# Solar_Power_Management_ESP32.net
KiCad netlist of a schematic drawn in EAGLE
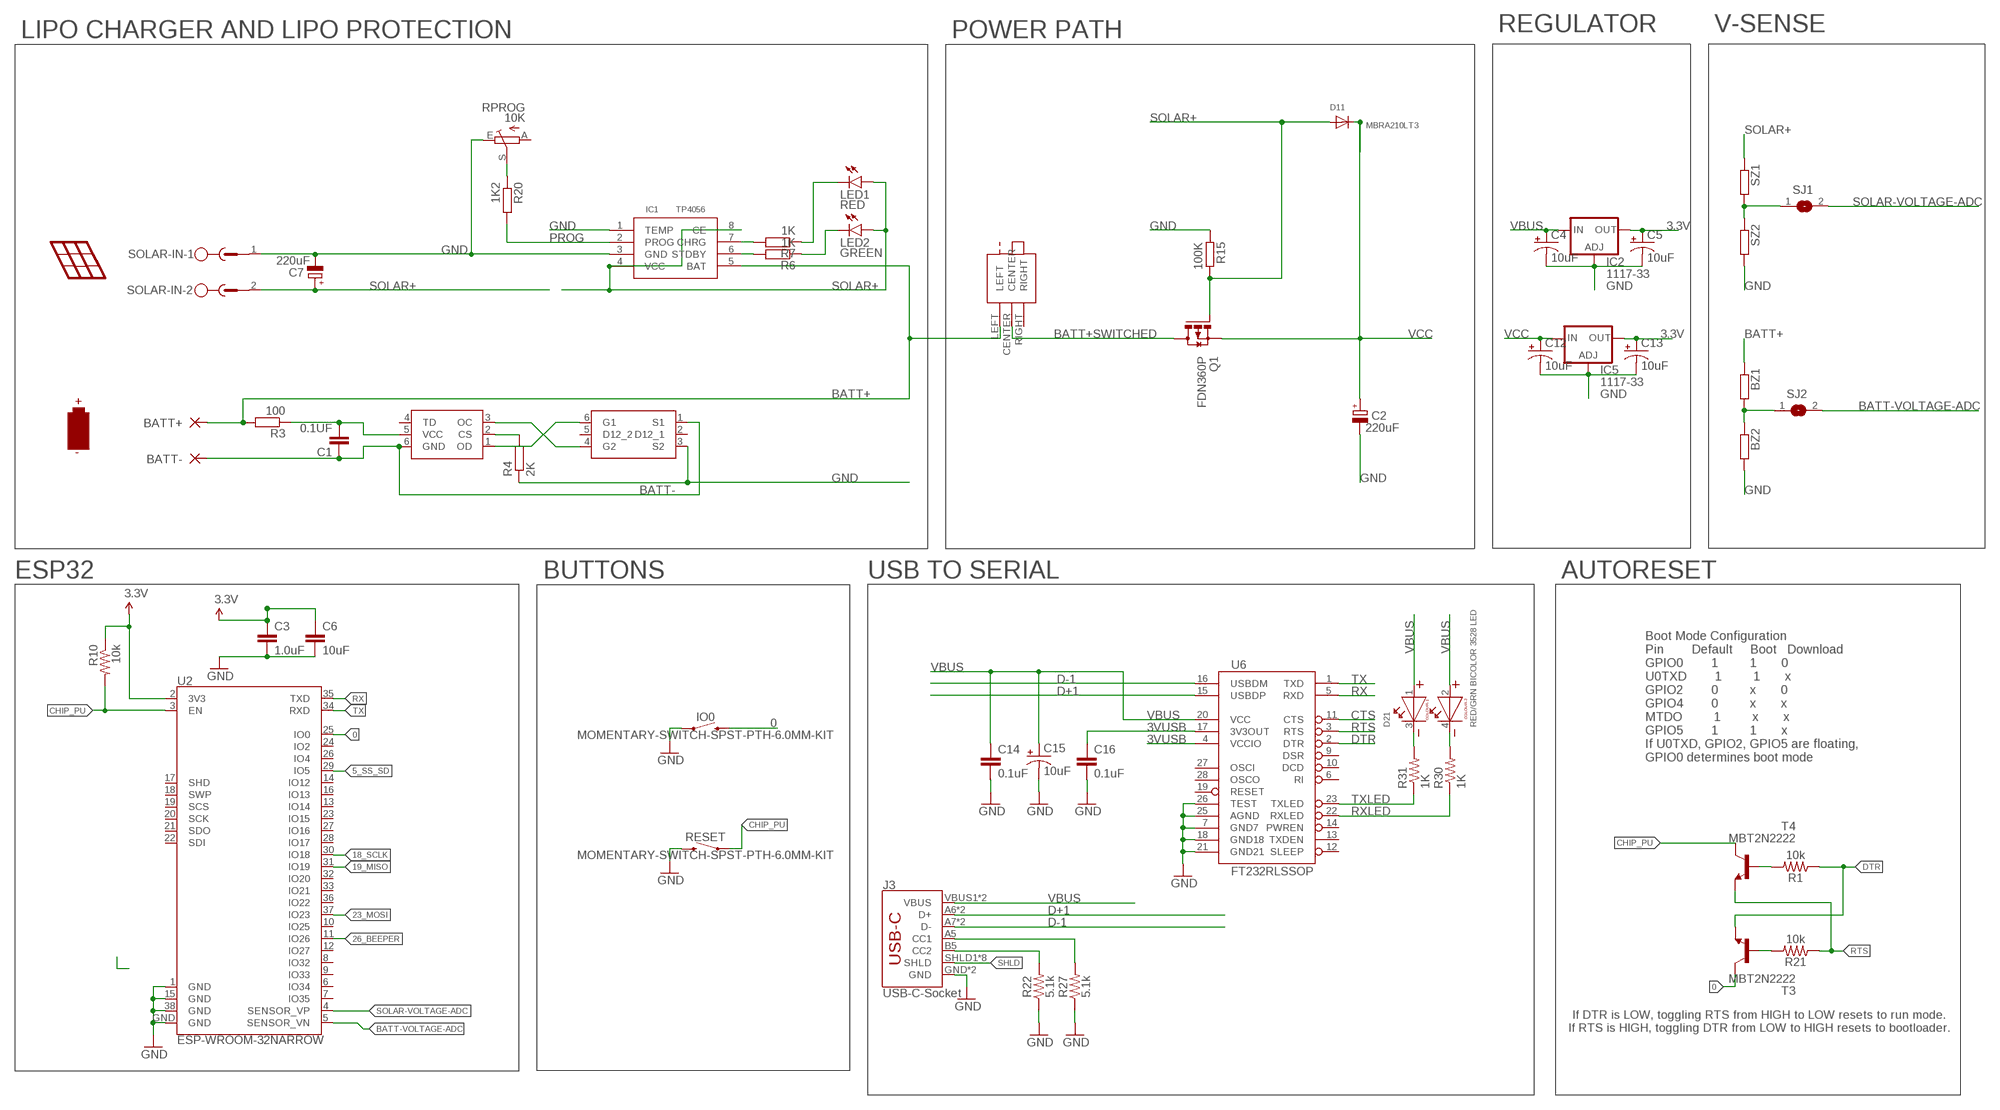
[diagram p0: schematic, sheet 1, part 1 of 2]
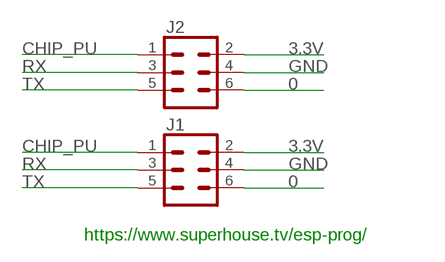
[diagram p1: schematic, sheet 1, part 2 of 2]

(export (version "E")
  (design (tool "Eeschema 10.0.6"))
  (components
    (comp (ref "BATT+")
      (value "3,81/1,4")
      (footprint "eagle-import:3,81_1,4")
      (libsource (lib "eagle-import") (part "3,81/1,4"))
    )
    (comp (ref "BATT-")
      (value "3,81/1,4")
      (footprint "eagle-import:3,81_1,4")
      (libsource (lib "eagle-import") (part "3,81/1,4"))
    )
    (comp (ref "BZ1")
      (value "R-EU_R1206")
      (footprint "eagle-import:R1206")
      (libsource (lib "eagle-import") (part "R-EU_R1206"))
    )
    (comp (ref "BZ2")
      (value "R-EU_R1206")
      (footprint "eagle-import:R1206")
      (libsource (lib "eagle-import") (part "R-EU_R1206"))
    )
    (comp (ref "C1")
      (value "0.1UF")
      (footprint "eagle-import:C1206")
      (libsource (lib "eagle-import") (part "C-EUC1206"))
    )
    (comp (ref "C2")
      (value "220uF")
      (footprint "eagle-import:E3,5-8")
      (libsource (lib "eagle-import") (part "CPOL-EUE3.5-8"))
    )
    (comp (ref "C3")
      (value "1.0uF")
      (footprint "eagle-import:1206")
      (libsource (lib "eagle-import") (part "1.0UF-1206-50V-10%"))
    )
    (comp (ref "C4")
      (value "10uF")
      (footprint "eagle-import:EIA3216")
      (libsource (lib "eagle-import") (part "CAP_POL1206"))
    )
    (comp (ref "C5")
      (value "10uF")
      (footprint "eagle-import:EIA3216")
      (libsource (lib "eagle-import") (part "CAP_POL1206"))
    )
    (comp (ref "C6")
      (value "10uF")
      (footprint "eagle-import:1206")
      (libsource (lib "eagle-import") (part "10UF-1206-6.3V-20%"))
    )
    (comp (ref "C7")
      (value "220uF")
      (footprint "eagle-import:E3,5-8")
      (libsource (lib "eagle-import") (part "CPOL-EUE3.5-8"))
    )
    (comp (ref "C12")
      (value "10uF")
      (footprint "eagle-import:EIA3216")
      (libsource (lib "eagle-import") (part "CAP_POL1206"))
    )
    (comp (ref "C13")
      (value "10uF")
      (footprint "eagle-import:EIA3216")
      (libsource (lib "eagle-import") (part "CAP_POL1206"))
    )
    (comp (ref "C14")
      (value "0.1uF")
      (footprint "eagle-import:0603-CAP")
      (libsource (lib "eagle-import") (part "CAP0603-CAP"))
    )
    (comp (ref "C15")
      (value "10uF")
      (footprint "eagle-import:EIA3216")
      (libsource (lib "eagle-import") (part "CAP_POL1206"))
    )
    (comp (ref "C16")
      (value "0.1uF")
      (footprint "eagle-import:0603-CAP")
      (libsource (lib "eagle-import") (part "CAP0603-CAP"))
    )
    (comp (ref "D11")
      (value "MBRA210LT3")
      (footprint "eagle-import:SMADIODE")
      (libsource (lib "eagle-import") (part "DIODESMA"))
    )
    (comp (ref "D21")
      (value "RED/GRN BICOLOR 3528 LED")
      (footprint "eagle-import:3528")
      (fields
        (field (name "MANUFACTURER") "Würth Elektronik eiSos GmbH")
        (field (name "CREATED-BY") "Christin Otto")
      )
      (libsource (lib "eagle-import") (part "WL-SBTW-150141RB73100-R&B"))
    )
    (comp (ref "IC1")
      (value "TP4056")
      (footprint "eagle-import:SOP-8")
      (libsource (lib "eagle-import") (part "TP4056"))
    )
    (comp (ref "IC2")
      (value "1117-33")
      (footprint "eagle-import:SOT223")
      (libsource (lib "eagle-import") (part "LD117A?S33TR"))
    )
    (comp (ref "IC5")
      (value "1117-33")
      (footprint "eagle-import:SOT223")
      (libsource (lib "eagle-import") (part "LD117A?S33TR"))
    )
    (comp (ref "IO0")
      (value "MOMENTARY-SWITCH-SPST-PTH-6.0MM-KIT")
      (footprint "eagle-import:TACTILE_SWITCH_PTH_6.0MM_KIT")
      (libsource (lib "eagle-import") (part "SparkFun-Switches_535_MOMENTARY-SWITCH-SPST-PTH-6.0MM-KIT"))
    )
    (comp (ref "J1")
      (value "CONN_03X2SHROUD")
      (footprint "eagle-import:2X3-SHROUDED")
      (libsource (lib "eagle-import") (part "CONN_03X2SHROUD"))
    )
    (comp (ref "J2")
      (value "CONN_03X2SHROUD")
      (footprint "eagle-import:2X3-SHROUDED")
      (libsource (lib "eagle-import") (part "CONN_03X2SHROUD"))
    )
    (comp (ref "J3")
      (value "USB-C-Socket")
      (footprint "eagle-import:USB-C-16P")
      (libsource (lib "eagle-import") (part "USB_C16PIN"))
    )
    (comp (ref "LED1")
      (value "RED")
      (footprint "eagle-import:CHIPLED_1206")
      (libsource (lib "eagle-import") (part "LEDCHIPLED_1206"))
    )
    (comp (ref "LED2")
      (value "GREEN")
      (footprint "eagle-import:CHIPLED_1206")
      (libsource (lib "eagle-import") (part "LEDCHIPLED_1206"))
    )
    (comp (ref "Q1")
      (value "FDN360P")
      (footprint "eagle-import:SUPER-SOT3")
      (libsource (lib "eagle-import") (part "FDN360P"))
    )
    (comp (ref "R1")
      (value "10k")
      (footprint "eagle-import:0603")
      (libsource (lib "eagle-import") (part "10KOHM-0603-1/10W-1%"))
    )
    (comp (ref "R3")
      (value "100")
      (footprint "eagle-import:R1206")
      (libsource (lib "eagle-import") (part "R-EU_R1206"))
    )
    (comp (ref "R4")
      (value "2K")
      (footprint "eagle-import:R1206")
      (libsource (lib "eagle-import") (part "R-EU_R1206"))
    )
    (comp (ref "R6")
      (value "1K")
      (footprint "eagle-import:R1206")
      (libsource (lib "eagle-import") (part "R-EU_R1206"))
    )
    (comp (ref "R7")
      (value "1K")
      (footprint "eagle-import:R1206")
      (libsource (lib "eagle-import") (part "R-EU_R1206"))
    )
    (comp (ref "R10")
      (value "10k")
      (footprint "eagle-import:R1206")
      (libsource (lib "eagle-import") (part "R-US_R1206"))
    )
    (comp (ref "R15")
      (value "100K")
      (footprint "eagle-import:R1206")
      (libsource (lib "eagle-import") (part "R-EU_R1206"))
    )
    (comp (ref "R20")
      (value "1K2")
      (footprint "eagle-import:R1206")
      (fields (field (name "SPICEPREFIX") "R"))
      (libsource (lib "eagle-import") (part "R-EU_R1206"))
    )
    (comp (ref "R21")
      (value "10k")
      (footprint "eagle-import:0603")
      (libsource (lib "eagle-import") (part "10KOHM-0603-1/10W-1%"))
    )
    (comp (ref "R22")
      (value "5.1k")
      (footprint "eagle-import:0603@1")
      (libsource (lib "eagle-import") (part "5.1KOHM5.1KOHM-0603-1/10W-1%"))
    )
    (comp (ref "R27")
      (value "5.1k")
      (footprint "eagle-import:0603@1")
      (libsource (lib "eagle-import") (part "5.1KOHM5.1KOHM-0603-1/10W-1%"))
    )
    (comp (ref "R30")
      (value "1K")
      (footprint "eagle-import:0603-RES")
      (libsource (lib "eagle-import") (part "RESISTOR0603-RES"))
    )
    (comp (ref "R31")
      (value "1K")
      (footprint "eagle-import:0603-RES")
      (libsource (lib "eagle-import") (part "RESISTOR0603-RES"))
    )
    (comp (ref "RESET")
      (value "MOMENTARY-SWITCH-SPST-PTH-6.0MM-KIT")
      (footprint "eagle-import:TACTILE_SWITCH_PTH_6.0MM_KIT")
      (libsource (lib "eagle-import") (part "MOMENTARY-SWITCH-SPST-PTH-6.0MM-KIT"))
    )
    (comp (ref "RPROG")
      (value "10K")
      (footprint "eagle-import:B25P")
      (libsource (lib "eagle-import") (part "TRIM_EU-B25P"))
    )
    (comp (ref "SJ1") (value "SJ") (footprint "eagle-import:SJ") (libsource (lib "eagle-import") (part "SJ")))
    (comp (ref "SJ2") (value "SJ") (footprint "eagle-import:SJ") (libsource (lib "eagle-import") (part "SJ")))
    (comp (ref "SOLAR-IN")
      (value "MSTBV2")
      (footprint "eagle-import:MSTBV2")
      (libsource (lib "eagle-import") (part "MSTBV2"))
    )
    (comp (ref "SZ1")
      (value "R-EU_R1206")
      (footprint "eagle-import:R1206")
      (libsource (lib "eagle-import") (part "R-EU_R1206"))
    )
    (comp (ref "SZ2")
      (value "R-EU_R1206")
      (footprint "eagle-import:R1206")
      (libsource (lib "eagle-import") (part "R-EU_R1206"))
    )
    (comp (ref "T3")
      (value "MBT2N2222")
      (footprint "eagle-import:SOT23-BEC")
      (libsource (lib "eagle-import") (part "-NPN-SOT23-BECMMBT2222ALT1"))
    )
    (comp (ref "T4")
      (value "MBT2N2222")
      (footprint "eagle-import:SOT23-BEC")
      (libsource (lib "eagle-import") (part "-NPN-SOT23-BECMMBT2222ALT1"))
    )
    (comp (ref "U$1")
      (value "FS312F-G")
      (footprint "eagle-import:SOT23-6")
      (libsource (lib "eagle-import") (part "FS312F-G"))
    )
    (comp (ref "U$2")
      (value "FS8205")
      (footprint "eagle-import:SOT23-6")
      (libsource (lib "eagle-import") (part "FS8205"))
    )
    (comp (ref "U$3")
      (value "XKBENTERPRISESS-12D11G5R")
      (footprint "eagle-import:XKBENTERPRISESS-12D11G5R")
      (libsource (lib "eagle-import") (part "XKBENTERPRISESS-12D11G5R"))
    )
    (comp (ref "U2")
      (value "ESP-WROOM-32NARROW")
      (footprint "eagle-import:ESP-WROOM-32-NARROW")
      (libsource (lib "eagle-import") (part "ESP-WROOM-32NARROW"))
    )
    (comp (ref "U6")
      (value "FT232RLSSOP")
      (footprint "eagle-import:SSOP28DB")
      (libsource (lib "eagle-import") (part "FT232RLSSOP"))
    )
  )
  (nets
    (net (code "1") (name "/3VUSB") (class "Default")
      (node (ref "C16") (pin "1") (pinfunction "1_1") (pintype "passive"))
      (node (ref "U6") (pin "17") (pinfunction "3V3OUT_17") (pintype "output"))
      (node (ref "U6") (pin "4") (pinfunction "VCCIO_4") (pintype "power_in"))
    )
    (net (code "2") (name "/BATT+") (class "Default")
      (node (ref "BATT+") (pin "1") (pinfunction "P_1") (pintype "passive"))
      (node (ref "BZ1") (pin "1") (pinfunction "1_1") (pintype "passive"))
      (node (ref "IC1") (pin "5") (pinfunction "BAT_5") (pintype "bidirectional"))
      (node (ref "R3") (pin "2") (pinfunction "2_2") (pintype "passive"))
      (node (ref "U$3") (pin "LEFT") (pinfunction "LEFT_LEFT") (pintype "bidirectional"))
    )
    (net (code "3") (name "/BATT+SWITCHED") (class "Default")
      (node (ref "Q1") (pin "3") (pinfunction "D_3") (pintype "passive"))
      (node (ref "U$3") (pin "CENTER") (pinfunction "CENTER_CENTER") (pintype "bidirectional"))
    )
    (net (code "4") (name "/BATT-") (class "Default")
      (node (ref "BATT-") (pin "1") (pinfunction "P_1") (pintype "passive"))
      (node (ref "C1") (pin "1") (pinfunction "1_1") (pintype "passive"))
      (node (ref "U$1") (pin "6") (pinfunction "GND_6") (pintype "bidirectional"))
      (node (ref "U$2") (pin "1") (pinfunction "S1_1") (pintype "bidirectional"))
    )
    (net (code "5") (name "/CTS") (class "Default")
      (node (ref "U6") (pin "11") (pinfunction "CTS_11") (pintype "input"))
    )
    (net (code "6") (name "/D+1") (class "Default")
      (node (ref "J3") (pin "A6") (pinfunction "D+_A6") (pintype "bidirectional"))
      (node (ref "J3") (pin "B6") (pinfunction "D+_B6") (pintype "bidirectional"))
      (node (ref "U6") (pin "15") (pinfunction "USBDP_15") (pintype "bidirectional"))
    )
    (net (code "7") (name "/D-1") (class "Default")
      (node (ref "J3") (pin "A7") (pinfunction "D-_A7") (pintype "bidirectional"))
      (node (ref "J3") (pin "B7") (pinfunction "D-_B7") (pintype "bidirectional"))
      (node (ref "U6") (pin "16") (pinfunction "USBDM_16") (pintype "bidirectional"))
    )
    (net (code "8") (name "/PROG") (class "Default")
      (node (ref "IC1") (pin "2") (pinfunction "PROG_2") (pintype "bidirectional"))
      (node (ref "R20") (pin "2") (pinfunction "2_2") (pintype "passive"))
    )
    (net (code "9") (name "/RXLED") (class "Default")
      (node (ref "R30") (pin "1") (pinfunction "1_1") (pintype "passive"))
      (node (ref "U6") (pin "22") (pinfunction "RXLED_22") (pintype "input"))
    )
    (net (code "10") (name "/SOLAR+") (class "Default")
      (node (ref "C7") (pin "+") (pinfunction "+_+") (pintype "passive"))
      (node (ref "D11") (pin "A") (pinfunction "A_A") (pintype "passive"))
      (node (ref "IC1") (pin "4") (pinfunction "VCC_4") (pintype "bidirectional"))
      (node (ref "IC1") (pin "8") (pinfunction "CE_8") (pintype "bidirectional"))
      (node (ref "LED1") (pin "A") (pinfunction "A_A") (pintype "passive"))
      (node (ref "LED2") (pin "A") (pinfunction "A_A") (pintype "passive"))
      (node (ref "Q1") (pin "1") (pinfunction "G_1") (pintype "passive"))
      (node (ref "R15") (pin "2") (pinfunction "2_2") (pintype "passive"))
      (node (ref "SOLAR-IN") (pin "2") (pinfunction "SK_2") (pintype "passive"))
      (node (ref "SZ1") (pin "1") (pinfunction "1_1") (pintype "passive"))
    )
    (net (code "11") (name "/TXLED") (class "Default")
      (node (ref "R31") (pin "1") (pinfunction "1_1") (pintype "passive"))
      (node (ref "U6") (pin "23") (pinfunction "TXLED_23") (pintype "input"))
    )
    (net (code "12") (name "/VBUS") (class "Default")
      (node (ref "C14") (pin "1") (pinfunction "1_1") (pintype "passive"))
      (node (ref "C15") (pin "A") (pinfunction "+_A") (pintype "passive"))
      (node (ref "C4") (pin "A") (pinfunction "+_A") (pintype "passive"))
      (node (ref "D21") (pin "1") (pinfunction "A1_1") (pintype "bidirectional"))
      (node (ref "D21") (pin "2") (pinfunction "A2_2") (pintype "bidirectional"))
      (node (ref "IC2") (pin "3") (pinfunction "IN_3") (pintype "input"))
      (node (ref "J3") (pin "VBUS1") (pinfunction "VBUS_VBUS1") (pintype "bidirectional"))
      (node (ref "J3") (pin "VBUS2") (pinfunction "VBUS_VBUS2") (pintype "bidirectional"))
      (node (ref "U6") (pin "20") (pinfunction "VCC_20") (pintype "power_in"))
    )
    (net (code "13") (name "/VCC") (class "Default")
      (node (ref "C12") (pin "A") (pinfunction "+_A") (pintype "passive"))
      (node (ref "C2") (pin "+") (pinfunction "+_+") (pintype "passive"))
      (node (ref "D11") (pin "C") (pinfunction "C_C") (pintype "passive"))
      (node (ref "IC5") (pin "3") (pinfunction "IN_3") (pintype "input"))
      (node (ref "Q1") (pin "2") (pinfunction "S_2") (pintype "passive"))
    )
    (net (code "14") (name "0") (class "Default")
      (node (ref "IO0") (pin "3") (pinfunction "2_3") (pintype "passive"))
      (node (ref "J1") (pin "6") (pinfunction "6_6") (pintype "bidirectional"))
      (node (ref "J2") (pin "6") (pinfunction "6_6") (pintype "bidirectional"))
      (node (ref "T3") (pin "C") (pinfunction "C_C") (pintype "passive"))
      (node (ref "U2") (pin "25") (pinfunction "IO0_25") (pintype "bidirectional"))
    )
    (net (code "15") (name "3.3V") (class "Default")
      (node (ref "C13") (pin "A") (pinfunction "+_A") (pintype "passive"))
      (node (ref "C3") (pin "1") (pinfunction "1_1") (pintype "passive"))
      (node (ref "C5") (pin "A") (pinfunction "+_A") (pintype "passive"))
      (node (ref "C6") (pin "1") (pinfunction "1_1") (pintype "passive"))
      (node (ref "IC2") (pin "4") (pinfunction "OUT_4") (pintype "passive"))
      (node (ref "IC5") (pin "4") (pinfunction "OUT_4") (pintype "passive"))
      (node (ref "J1") (pin "2") (pinfunction "2_2") (pintype "bidirectional"))
      (node (ref "J2") (pin "2") (pinfunction "2_2") (pintype "bidirectional"))
      (node (ref "R10") (pin "1") (pinfunction "1_1") (pintype "passive"))
      (node (ref "U2") (pin "2") (pinfunction "3V3_2") (pintype "bidirectional"))
    )
    (net (code "16") (name "5_SS_SD") (class "Default")
      (node (ref "U2") (pin "29") (pinfunction "IO5_29") (pintype "bidirectional"))
    )
    (net (code "17") (name "18_SCLK") (class "Default")
      (node (ref "U2") (pin "30") (pinfunction "IO18_30") (pintype "bidirectional"))
    )
    (net (code "18") (name "19_MISO") (class "Default")
      (node (ref "U2") (pin "31") (pinfunction "IO19_31") (pintype "bidirectional"))
    )
    (net (code "19") (name "23_MOSI") (class "Default")
      (node (ref "U2") (pin "37") (pinfunction "IO23_37") (pintype "bidirectional"))
    )
    (net (code "20") (name "26_BEEPER") (class "Default")
      (node (ref "U2") (pin "11") (pinfunction "IO26_11") (pintype "bidirectional"))
    )
    (net (code "21") (name "BATT-VOLTAGE-ADC") (class "Default")
      (node (ref "BZ1") (pin "2") (pinfunction "2_2") (pintype "passive"))
      (node (ref "BZ2") (pin "1") (pinfunction "1_1") (pintype "passive"))
      (node (ref "SJ2") (pin "1") (pinfunction "1_1") (pintype "passive"))
      (node (ref "SJ2") (pin "2") (pinfunction "2_2") (pintype "passive"))
      (node (ref "U2") (pin "5") (pinfunction "SENSOR_VN_5") (pintype "bidirectional"))
    )
    (net (code "22") (name "CHIP_PU") (class "Default")
      (node (ref "J1") (pin "1") (pinfunction "1_1") (pintype "bidirectional"))
      (node (ref "J2") (pin "1") (pinfunction "1_1") (pintype "bidirectional"))
      (node (ref "R10") (pin "2") (pinfunction "2_2") (pintype "passive"))
      (node (ref "RESET") (pin "1") (pinfunction "1_1") (pintype "passive"))
      (node (ref "T4") (pin "C") (pinfunction "C_C") (pintype "passive"))
      (node (ref "U2") (pin "3") (pinfunction "EN_3") (pintype "bidirectional"))
    )
    (net (code "23") (name "DTR") (class "Default")
      (node (ref "R1") (pin "1") (pinfunction "1_1") (pintype "passive"))
      (node (ref "T3") (pin "E") (pinfunction "E_E") (pintype "passive"))
      (node (ref "U6") (pin "2") (pinfunction "DTR_2") (pintype "output"))
    )
    (net (code "24") (name "GND") (class "Default")
      (node (ref "BZ2") (pin "2") (pinfunction "2_2") (pintype "passive"))
      (node (ref "C12") (pin "C") (pinfunction "-_C") (pintype "passive"))
      (node (ref "C13") (pin "C") (pinfunction "-_C") (pintype "passive"))
      (node (ref "C14") (pin "2") (pinfunction "2_2") (pintype "passive"))
      (node (ref "C15") (pin "C") (pinfunction "-_C") (pintype "passive"))
      (node (ref "C16") (pin "2") (pinfunction "2_2") (pintype "passive"))
      (node (ref "C2") (pin "-") (pinfunction "-_-") (pintype "passive"))
      (node (ref "C3") (pin "2") (pinfunction "2_2") (pintype "passive"))
      (node (ref "C4") (pin "C") (pinfunction "-_C") (pintype "passive"))
      (node (ref "C5") (pin "C") (pinfunction "-_C") (pintype "passive"))
      (node (ref "C6") (pin "2") (pinfunction "2_2") (pintype "passive"))
      (node (ref "C7") (pin "-") (pinfunction "-_-") (pintype "passive"))
      (node (ref "IC1") (pin "1") (pinfunction "TEMP_1") (pintype "bidirectional"))
      (node (ref "IC1") (pin "3") (pinfunction "GND_3") (pintype "bidirectional"))
      (node (ref "IC2") (pin "1") (pinfunction "ADJ_1") (pintype "input"))
      (node (ref "IC5") (pin "1") (pinfunction "ADJ_1") (pintype "input"))
      (node (ref "IO0") (pin "1") (pinfunction "1_1") (pintype "passive"))
      (node (ref "J1") (pin "4") (pinfunction "4_4") (pintype "bidirectional"))
      (node (ref "J2") (pin "4") (pinfunction "4_4") (pintype "bidirectional"))
      (node (ref "J3") (pin "GND") (pinfunction "GND_GND") (pintype "bidirectional"))
      (node (ref "J3") (pin "GND2") (pinfunction "GND_GND2") (pintype "bidirectional"))
      (node (ref "R15") (pin "1") (pinfunction "1_1") (pintype "passive"))
      (node (ref "R22") (pin "1") (pinfunction "1_1") (pintype "passive"))
      (node (ref "R27") (pin "1") (pinfunction "1_1") (pintype "passive"))
      (node (ref "R4") (pin "1") (pinfunction "1_1") (pintype "passive"))
      (node (ref "RESET") (pin "3") (pinfunction "2_3") (pintype "passive"))
      (node (ref "RPROG") (pin "E") (pinfunction "E_E") (pintype "passive"))
      (node (ref "SOLAR-IN") (pin "1") (pinfunction "SK_1") (pintype "passive"))
      (node (ref "SZ2") (pin "2") (pinfunction "2_2") (pintype "passive"))
      (node (ref "U$2") (pin "3") (pinfunction "S2_3") (pintype "bidirectional"))
      (node (ref "U2") (pin "1") (pinfunction "GND_1") (pintype "bidirectional"))
      (node (ref "U2") (pin "15") (pinfunction "GND_15") (pintype "bidirectional"))
      (node (ref "U2") (pin "38") (pinfunction "GND_38") (pintype "bidirectional"))
      (node (ref "U2") (pin "GND") (pinfunction "GND_GND") (pintype "bidirectional"))
      (node (ref "U6") (pin "18") (pinfunction "GND18_18") (pintype "power_in"))
      (node (ref "U6") (pin "21") (pinfunction "GND21_21") (pintype "power_in"))
      (node (ref "U6") (pin "25") (pinfunction "AGND_25") (pintype "power_in"))
      (node (ref "U6") (pin "26") (pinfunction "TEST_26") (pintype "input"))
      (node (ref "U6") (pin "7") (pinfunction "GND7_7") (pintype "power_in"))
    )
    (net (code "25") (name "Net-(D21-C1)") (class "Default")
      (node (ref "D21") (pin "3") (pinfunction "C1_3") (pintype "bidirectional"))
      (node (ref "R31") (pin "2") (pinfunction "2_2") (pintype "passive"))
    )
    (net (code "26") (name "Net-(D21-C2)") (class "Default")
      (node (ref "D21") (pin "4") (pinfunction "C2_4") (pintype "bidirectional"))
      (node (ref "R30") (pin "2") (pinfunction "2_2") (pintype "passive"))
    )
    (net (code "27") (name "Net-(IC1-CHRG)") (class "Default")
      (node (ref "IC1") (pin "7") (pinfunction "CHRG_7") (pintype "bidirectional"))
      (node (ref "R7") (pin "2") (pinfunction "2_2") (pintype "passive"))
    )
    (net (code "28") (name "Net-(IC1-STDBY)") (class "Default")
      (node (ref "IC1") (pin "6") (pinfunction "STDBY_6") (pintype "bidirectional"))
      (node (ref "R6") (pin "2") (pinfunction "2_2") (pintype "passive"))
    )
    (net (code "29") (name "Net-(J3-CC1)") (class "Default")
      (node (ref "J3") (pin "A5") (pinfunction "CC1_A5") (pintype "bidirectional"))
      (node (ref "R27") (pin "2") (pinfunction "2_2") (pintype "passive"))
    )
    (net (code "30") (name "Net-(J3-CC2)") (class "Default")
      (node (ref "J3") (pin "B5") (pinfunction "CC2_B5") (pintype "bidirectional"))
      (node (ref "R22") (pin "2") (pinfunction "2_2") (pintype "passive"))
    )
    (net (code "31") (name "Net-(LED1-PadC)") (class "Default")
      (node (ref "LED1") (pin "C") (pinfunction "C_C") (pintype "passive"))
      (node (ref "R7") (pin "1") (pinfunction "1_1") (pintype "passive"))
    )
    (net (code "32") (name "Net-(LED2-PadC)") (class "Default")
      (node (ref "LED2") (pin "C") (pinfunction "C_C") (pintype "passive"))
      (node (ref "R6") (pin "1") (pinfunction "1_1") (pintype "passive"))
    )
    (net (code "33") (name "Net-(R1-Pad2)") (class "Default")
      (node (ref "R1") (pin "2") (pinfunction "2_2") (pintype "passive"))
      (node (ref "T4") (pin "B") (pinfunction "B_B") (pintype "passive"))
    )
    (net (code "34") (name "Net-(R20-Pad1)") (class "Default")
      (node (ref "R20") (pin "1") (pinfunction "1_1") (pintype "passive"))
      (node (ref "RPROG") (pin "S") (pinfunction "S_S") (pintype "passive"))
    )
    (net (code "35") (name "Net-(R21-Pad2)") (class "Default")
      (node (ref "R21") (pin "2") (pinfunction "2_2") (pintype "passive"))
      (node (ref "T3") (pin "B") (pinfunction "B_B") (pintype "passive"))
    )
    (net (code "36") (name "Net-(U$1-CS)") (class "Default")
      (node (ref "R4") (pin "2") (pinfunction "2_2") (pintype "passive"))
      (node (ref "U$1") (pin "2") (pinfunction "CS_2") (pintype "bidirectional"))
    )
    (net (code "37") (name "Net-(U$1-OC)") (class "Default")
      (node (ref "U$1") (pin "3") (pinfunction "OC_3") (pintype "bidirectional"))
      (node (ref "U$2") (pin "4") (pinfunction "G2_4") (pintype "bidirectional"))
    )
    (net (code "38") (name "Net-(U$1-OD)") (class "Default")
      (node (ref "U$1") (pin "1") (pinfunction "OD_1") (pintype "bidirectional"))
      (node (ref "U$2") (pin "6") (pinfunction "G1_6") (pintype "bidirectional"))
    )
    (net (code "39") (name "Net-(U$1-VCC)") (class "Default")
      (node (ref "C1") (pin "2") (pinfunction "2_2") (pintype "passive"))
      (node (ref "R3") (pin "1") (pinfunction "1_1") (pintype "passive"))
      (node (ref "U$1") (pin "5") (pinfunction "VCC_5") (pintype "bidirectional"))
    )
    (net (code "40") (name "RTS") (class "Default")
      (node (ref "R21") (pin "1") (pinfunction "1_1") (pintype "passive"))
      (node (ref "T4") (pin "E") (pinfunction "E_E") (pintype "passive"))
      (node (ref "U6") (pin "3") (pinfunction "RTS_3") (pintype "output"))
    )
    (net (code "41") (name "RX") (class "Default")
      (node (ref "J1") (pin "3") (pinfunction "3_3") (pintype "bidirectional"))
      (node (ref "J2") (pin "3") (pinfunction "3_3") (pintype "bidirectional"))
      (node (ref "U2") (pin "35") (pinfunction "TXD_35") (pintype "bidirectional"))
      (node (ref "U6") (pin "5") (pinfunction "RXD_5") (pintype "input"))
    )
    (net (code "42") (name "SHLD") (class "Default")
      (node (ref "J3") (pin "SHLD1") (pinfunction "SHLD_SHLD1") (pintype "bidirectional"))
      (node (ref "J3") (pin "SHLD2") (pinfunction "SHLD_SHLD2") (pintype "bidirectional"))
      (node (ref "J3") (pin "SHLD3") (pinfunction "SHLD_SHLD3") (pintype "bidirectional"))
      (node (ref "J3") (pin "SHLD4") (pinfunction "SHLD_SHLD4") (pintype "bidirectional"))
      (node (ref "J3") (pin "SHLD5") (pinfunction "SHLD_SHLD5") (pintype "bidirectional"))
      (node (ref "J3") (pin "SHLD6") (pinfunction "SHLD_SHLD6") (pintype "bidirectional"))
      (node (ref "J3") (pin "SHLD7") (pinfunction "SHLD_SHLD7") (pintype "bidirectional"))
      (node (ref "J3") (pin "SHLD8") (pinfunction "SHLD_SHLD8") (pintype "bidirectional"))
    )
    (net (code "43") (name "SOLAR-VOLTAGE-ADC") (class "Default")
      (node (ref "SJ1") (pin "1") (pinfunction "1_1") (pintype "passive"))
      (node (ref "SJ1") (pin "2") (pinfunction "2_2") (pintype "passive"))
      (node (ref "SZ1") (pin "2") (pinfunction "2_2") (pintype "passive"))
      (node (ref "SZ2") (pin "1") (pinfunction "1_1") (pintype "passive"))
      (node (ref "U2") (pin "4") (pinfunction "SENSOR_VP_4") (pintype "bidirectional"))
    )
    (net (code "44") (name "TX") (class "Default")
      (node (ref "J1") (pin "5") (pinfunction "5_5") (pintype "bidirectional"))
      (node (ref "J2") (pin "5") (pinfunction "5_5") (pintype "bidirectional"))
      (node (ref "U2") (pin "34") (pinfunction "RXD_34") (pintype "bidirectional"))
      (node (ref "U6") (pin "1") (pinfunction "TXD_1") (pintype "output"))
    )
    (net (code "45") (name "unconnected-(RPROG-PadA)") (class "Default")
      (node (ref "RPROG") (pin "A") (pinfunction "A_A") (pintype "passive"))
    )
    (net (code "46") (name "unconnected-(U$1-TD-Pad4)") (class "Default")
      (node (ref "U$1") (pin "4") (pinfunction "TD_4") (pintype "bidirectional"))
    )
    (net (code "47") (name "unconnected-(U$2-D12_1-Pad2)") (class "Default")
      (node (ref "U$2") (pin "2") (pinfunction "D12_1_2") (pintype "bidirectional"))
    )
    (net (code "48") (name "unconnected-(U$2-D12_2-Pad5)") (class "Default")
      (node (ref "U$2") (pin "5") (pinfunction "D12_2_5") (pintype "bidirectional"))
    )
    (net (code "49") (name "unconnected-(U$3-PadRIGHT)") (class "Default")
      (node (ref "U$3") (pin "RIGHT") (pinfunction "RIGHT_RIGHT") (pintype "bidirectional"))
    )
    (net (code "50") (name "unconnected-(U2-IO2-Pad24)") (class "Default")
      (node (ref "U2") (pin "24") (pinfunction "IO2_24") (pintype "bidirectional"))
    )
    (net (code "51") (name "unconnected-(U2-IO4-Pad26)") (class "Default")
      (node (ref "U2") (pin "26") (pinfunction "IO4_26") (pintype "bidirectional"))
    )
    (net (code "52") (name "unconnected-(U2-IO12-Pad14)") (class "Default")
      (node (ref "U2") (pin "14") (pinfunction "IO12_14") (pintype "bidirectional"))
    )
    (net (code "53") (name "unconnected-(U2-IO13-Pad16)") (class "Default")
      (node (ref "U2") (pin "16") (pinfunction "IO13_16") (pintype "bidirectional"))
    )
    (net (code "54") (name "unconnected-(U2-IO14-Pad13)") (class "Default")
      (node (ref "U2") (pin "13") (pinfunction "IO14_13") (pintype "bidirectional"))
    )
    (net (code "55") (name "unconnected-(U2-IO15-Pad23)") (class "Default")
      (node (ref "U2") (pin "23") (pinfunction "IO15_23") (pintype "bidirectional"))
    )
    (net (code "56") (name "unconnected-(U2-IO16-Pad27)") (class "Default")
      (node (ref "U2") (pin "27") (pinfunction "IO16_27") (pintype "bidirectional"))
    )
    (net (code "57") (name "unconnected-(U2-IO17-Pad28)") (class "Default")
      (node (ref "U2") (pin "28") (pinfunction "IO17_28") (pintype "bidirectional"))
    )
    (net (code "58") (name "unconnected-(U2-IO20-Pad32)") (class "Default")
      (node (ref "U2") (pin "32") (pinfunction "IO20_32") (pintype "bidirectional"))
    )
    (net (code "59") (name "unconnected-(U2-IO21-Pad33)") (class "Default")
      (node (ref "U2") (pin "33") (pinfunction "IO21_33") (pintype "bidirectional"))
    )
    (net (code "60") (name "unconnected-(U2-IO22-Pad36)") (class "Default")
      (node (ref "U2") (pin "36") (pinfunction "IO22_36") (pintype "bidirectional"))
    )
    (net (code "61") (name "unconnected-(U2-IO25-Pad10)") (class "Default")
      (node (ref "U2") (pin "10") (pinfunction "IO25_10") (pintype "bidirectional"))
    )
    (net (code "62") (name "unconnected-(U2-IO27-Pad12)") (class "Default")
      (node (ref "U2") (pin "12") (pinfunction "IO27_12") (pintype "bidirectional"))
    )
    (net (code "63") (name "unconnected-(U2-IO32-Pad8)") (class "Default")
      (node (ref "U2") (pin "8") (pinfunction "IO32_8") (pintype "bidirectional"))
    )
    (net (code "64") (name "unconnected-(U2-IO33-Pad9)") (class "Default")
      (node (ref "U2") (pin "9") (pinfunction "IO33_9") (pintype "bidirectional"))
    )
    (net (code "65") (name "unconnected-(U2-IO34-Pad6)") (class "Default")
      (node (ref "U2") (pin "6") (pinfunction "IO34_6") (pintype "bidirectional"))
    )
    (net (code "66") (name "unconnected-(U2-IO35-Pad7)") (class "Default")
      (node (ref "U2") (pin "7") (pinfunction "IO35_7") (pintype "bidirectional"))
    )
    (net (code "67") (name "unconnected-(U2-SCK-Pad20)") (class "Default")
      (node (ref "U2") (pin "20") (pinfunction "SCK_20") (pintype "bidirectional"))
    )
    (net (code "68") (name "unconnected-(U2-SCS-Pad19)") (class "Default")
      (node (ref "U2") (pin "19") (pinfunction "SCS_19") (pintype "bidirectional"))
    )
    (net (code "69") (name "unconnected-(U2-SDI-Pad22)") (class "Default")
      (node (ref "U2") (pin "22") (pinfunction "SDI_22") (pintype "bidirectional"))
    )
    (net (code "70") (name "unconnected-(U2-SDO-Pad21)") (class "Default")
      (node (ref "U2") (pin "21") (pinfunction "SDO_21") (pintype "bidirectional"))
    )
    (net (code "71") (name "unconnected-(U2-SHD-Pad17)") (class "Default")
      (node (ref "U2") (pin "17") (pinfunction "SHD_17") (pintype "bidirectional"))
    )
    (net (code "72") (name "unconnected-(U2-SWP-Pad18)") (class "Default")
      (node (ref "U2") (pin "18") (pinfunction "SWP_18") (pintype "bidirectional"))
    )
    (net (code "73") (name "unconnected-(U6-DCD-Pad10)") (class "Default")
      (node (ref "U6") (pin "10") (pinfunction "DCD_10") (pintype "input"))
    )
    (net (code "74") (name "unconnected-(U6-DSR-Pad9)") (class "Default")
      (node (ref "U6") (pin "9") (pinfunction "DSR_9") (pintype "input"))
    )
    (net (code "75") (name "unconnected-(U6-OSCI-Pad27)") (class "Default")
      (node (ref "U6") (pin "27") (pinfunction "OSCI_27") (pintype "input"))
    )
    (net (code "76") (name "unconnected-(U6-OSCO-Pad28)") (class "Default")
      (node (ref "U6") (pin "28") (pinfunction "OSCO_28") (pintype "output"))
    )
    (net (code "77") (name "unconnected-(U6-PWREN-Pad14)") (class "Default")
      (node (ref "U6") (pin "14") (pinfunction "PWREN_14") (pintype "input"))
    )
    (net (code "78") (name "unconnected-(U6-RESET-Pad19)") (class "Default")
      (node (ref "U6") (pin "19") (pinfunction "RESET_19") (pintype "input"))
    )
    (net (code "79") (name "unconnected-(U6-RI-Pad6)") (class "Default")
      (node (ref "U6") (pin "6") (pinfunction "RI_6") (pintype "input"))
    )
    (net (code "80") (name "unconnected-(U6-SLEEP-Pad12)") (class "Default")
      (node (ref "U6") (pin "12") (pinfunction "SLEEP_12") (pintype "input"))
    )
    (net (code "81") (name "unconnected-(U6-TXDEN-Pad13)") (class "Default")
      (node (ref "U6") (pin "13") (pinfunction "TXDEN_13") (pintype "input"))
    )
  )
)
